# eCog118_Switches.net
KiCad netlist of a schematic drawn in EAGLE
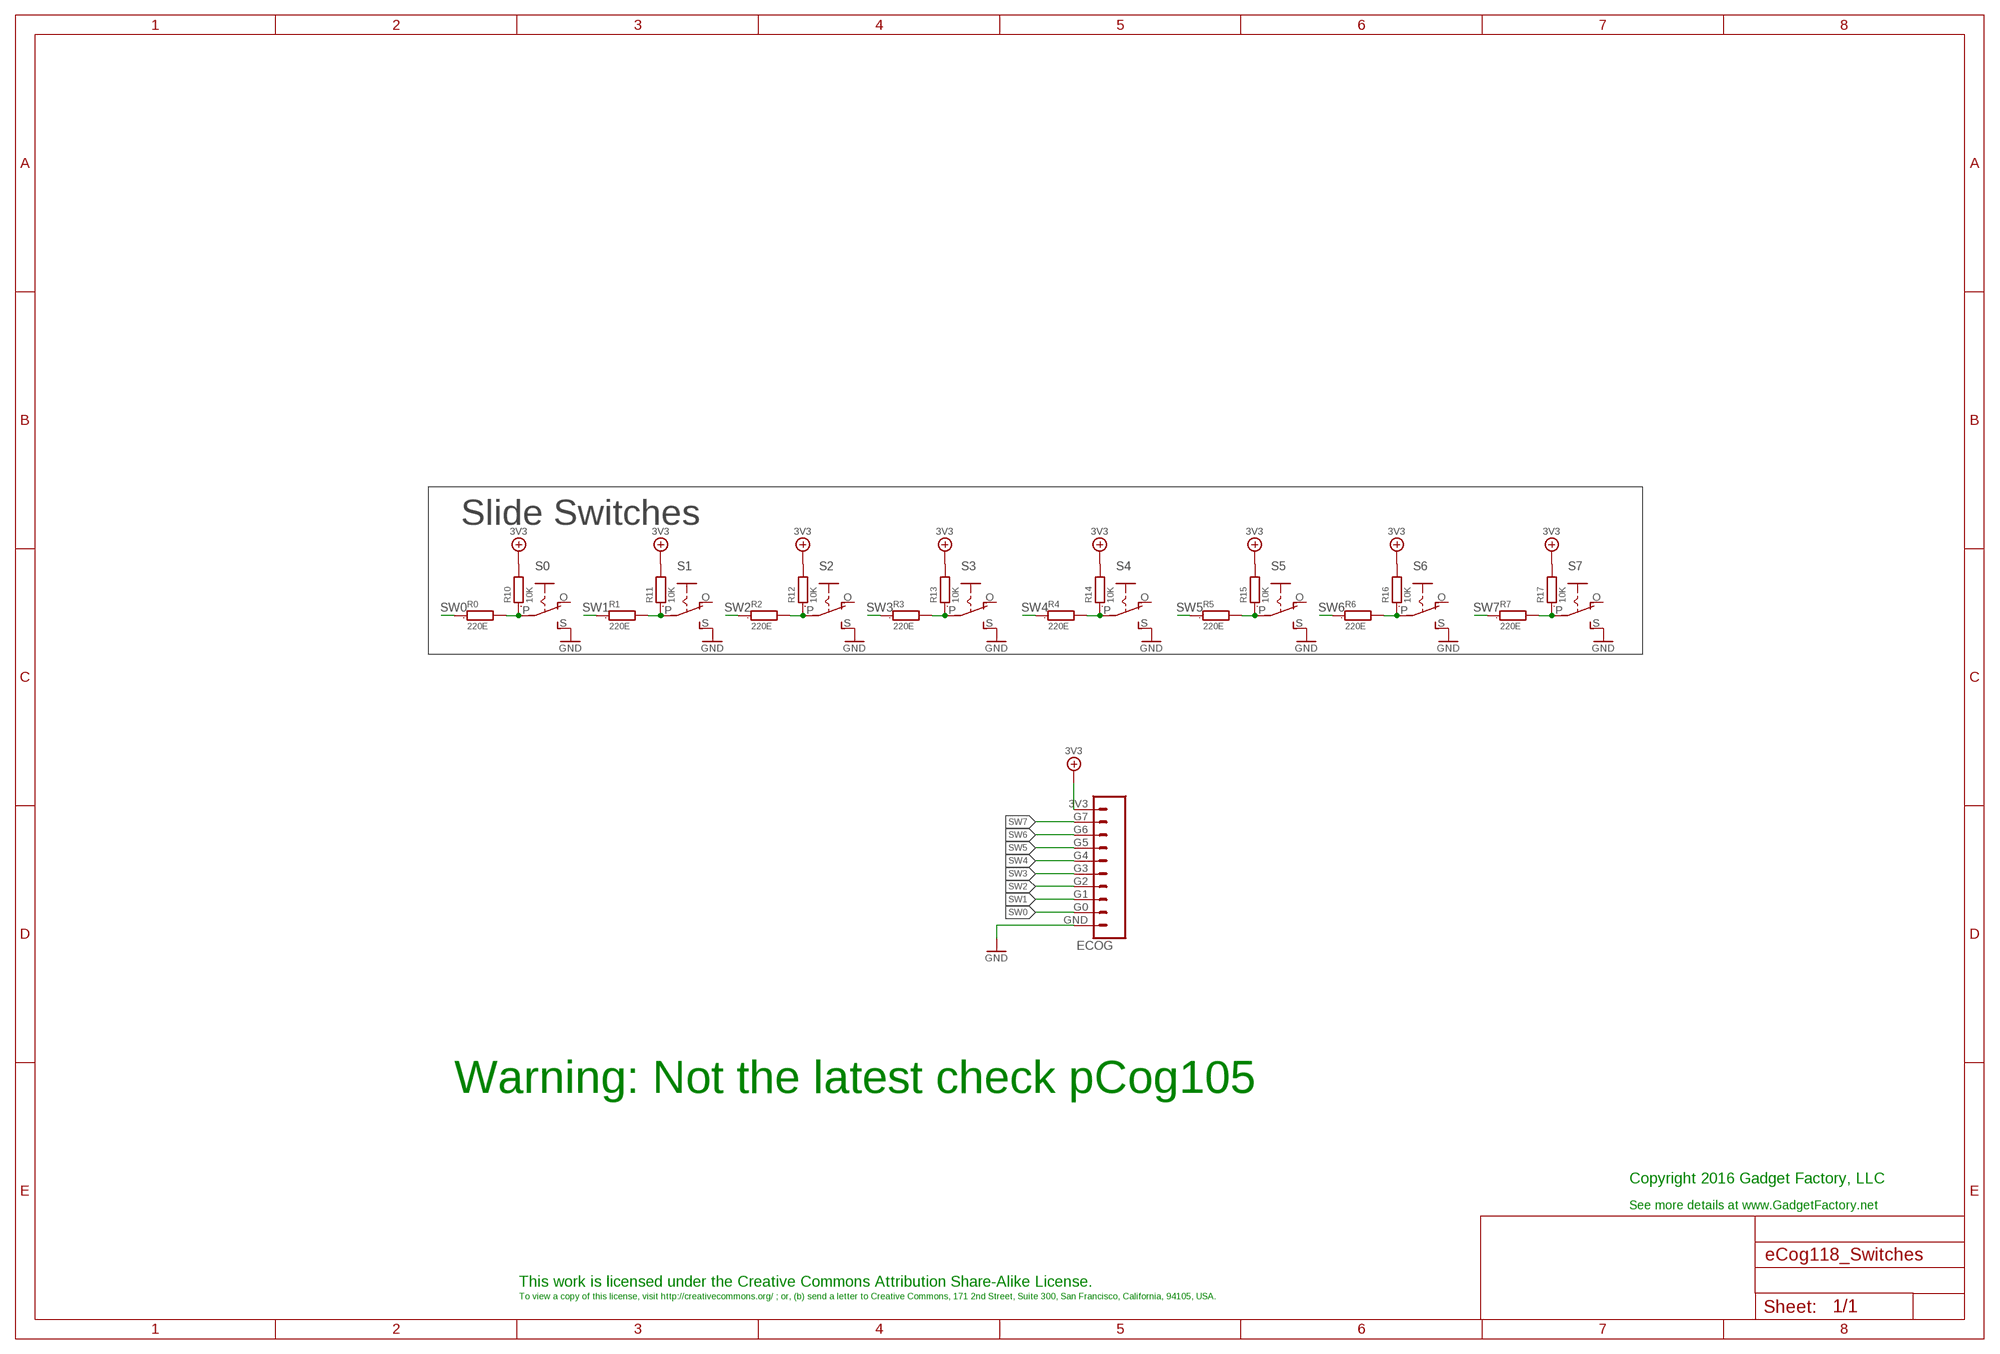
[diagram p0: schematic, sheet 1]

(export (version "E")
  (design (tool "Eeschema 10.0.6"))
  (components
    (comp (ref "ECOG")
      (value "ECOG_GENERAL_ROWTHROUGHOLE")
      (footprint "eagle-import:ECOG_GENERAL_TH")
      (libsource (lib "eagle-import") (part "ECOG_GENERAL_ROWTHROUGHOLE"))
    )
    (comp (ref "R0")
      (value "220E")
      (footprint "eagle-import:0603")
      (fields (field (name "PARTNO") "RMCF0603JT220R"))
      (libsource (lib "eagle-import") (part "R0603"))
    )
    (comp (ref "R1")
      (value "220E")
      (footprint "eagle-import:0603")
      (fields (field (name "PARTNO") "RMCF0603JT220R"))
      (libsource (lib "eagle-import") (part "R0603"))
    )
    (comp (ref "R2")
      (value "220E")
      (footprint "eagle-import:0603")
      (fields (field (name "PARTNO") "RMCF0603JT220R"))
      (libsource (lib "eagle-import") (part "R0603"))
    )
    (comp (ref "R3")
      (value "220E")
      (footprint "eagle-import:0603")
      (fields (field (name "PARTNO") "RMCF0603JT220R"))
      (libsource (lib "eagle-import") (part "R0603"))
    )
    (comp (ref "R4")
      (value "220E")
      (footprint "eagle-import:0603")
      (fields (field (name "PARTNO") "RMCF0603JT220R"))
      (libsource (lib "eagle-import") (part "R0603"))
    )
    (comp (ref "R5")
      (value "220E")
      (footprint "eagle-import:0603")
      (fields (field (name "PARTNO") "RMCF0603JT220R"))
      (libsource (lib "eagle-import") (part "R0603"))
    )
    (comp (ref "R6")
      (value "220E")
      (footprint "eagle-import:0603")
      (fields (field (name "PARTNO") "RMCF0603JT220R"))
      (libsource (lib "eagle-import") (part "R0603"))
    )
    (comp (ref "R7")
      (value "220E")
      (footprint "eagle-import:0603")
      (fields (field (name "PARTNO") "RMCF0603JT220R"))
      (libsource (lib "eagle-import") (part "R0603"))
    )
    (comp (ref "R10")
      (value "10K")
      (footprint "eagle-import:0603")
      (fields (field (name "PARTNO") "RMCF0603JT10K0"))
      (libsource (lib "eagle-import") (part "R0603"))
    )
    (comp (ref "R11")
      (value "10K")
      (footprint "eagle-import:0603")
      (fields (field (name "PARTNO") "RMCF0603JT10K0"))
      (libsource (lib "eagle-import") (part "R0603"))
    )
    (comp (ref "R12")
      (value "10K")
      (footprint "eagle-import:0603")
      (fields (field (name "PARTNO") "RMCF0603JT10K0"))
      (libsource (lib "eagle-import") (part "R0603"))
    )
    (comp (ref "R13")
      (value "10K")
      (footprint "eagle-import:0603")
      (fields (field (name "PARTNO") "RMCF0603JT10K0"))
      (libsource (lib "eagle-import") (part "R0603"))
    )
    (comp (ref "R14")
      (value "10K")
      (footprint "eagle-import:0603")
      (fields (field (name "PARTNO") "RMCF0603JT10K0"))
      (libsource (lib "eagle-import") (part "R0603"))
    )
    (comp (ref "R15")
      (value "10K")
      (footprint "eagle-import:0603")
      (fields (field (name "PARTNO") "RMCF0603JT10K0"))
      (libsource (lib "eagle-import") (part "R0603"))
    )
    (comp (ref "R16")
      (value "10K")
      (footprint "eagle-import:0603")
      (fields (field (name "PARTNO") "RMCF0603JT10K0"))
      (libsource (lib "eagle-import") (part "R0603"))
    )
    (comp (ref "R17")
      (value "10K")
      (footprint "eagle-import:0603")
      (fields (field (name "PARTNO") "RMCF0603JT10K0"))
      (libsource (lib "eagle-import") (part "R0603"))
    )
    (comp (ref "S0")
      (value "EG1218S")
      (footprint "eagle-import:EG1218")
      (fields (field (name "PARTNO") "EG1218"))
      (libsource (lib "eagle-import") (part "EG1218S"))
    )
    (comp (ref "S1")
      (value "EG1218S")
      (footprint "eagle-import:EG1218")
      (fields (field (name "PARTNO") "EG1218"))
      (libsource (lib "eagle-import") (part "EG1218S"))
    )
    (comp (ref "S2")
      (value "EG1218S")
      (footprint "eagle-import:EG1218")
      (fields (field (name "PARTNO") "EG1218"))
      (libsource (lib "eagle-import") (part "EG1218S"))
    )
    (comp (ref "S3")
      (value "EG1218S")
      (footprint "eagle-import:EG1218")
      (fields (field (name "PARTNO") "EG1218"))
      (libsource (lib "eagle-import") (part "EG1218S"))
    )
    (comp (ref "S4")
      (value "EG1218S")
      (footprint "eagle-import:EG1218")
      (fields (field (name "PARTNO") "EG1218"))
      (libsource (lib "eagle-import") (part "EG1218S"))
    )
    (comp (ref "S5")
      (value "EG1218S")
      (footprint "eagle-import:EG1218")
      (fields (field (name "PARTNO") "EG1218"))
      (libsource (lib "eagle-import") (part "EG1218S"))
    )
    (comp (ref "S6")
      (value "EG1218S")
      (footprint "eagle-import:EG1218")
      (fields (field (name "PARTNO") "EG1218"))
      (libsource (lib "eagle-import") (part "EG1218S"))
    )
    (comp (ref "S7")
      (value "EG1218S")
      (footprint "eagle-import:EG1218")
      (fields (field (name "PARTNO") "EG1218"))
      (libsource (lib "eagle-import") (part "EG1218S"))
    )
  )
  (nets
    (net (code "1") (name "3V3") (class "Default")
      (node (ref "ECOG") (pin "3V3") (pinfunction "3V3_3V3") (pintype "power_in"))
      (node (ref "R10") (pin "2") (pinfunction "2_2") (pintype "passive"))
      (node (ref "R11") (pin "2") (pinfunction "2_2") (pintype "passive"))
      (node (ref "R12") (pin "2") (pinfunction "2_2") (pintype "passive"))
      (node (ref "R13") (pin "2") (pinfunction "2_2") (pintype "passive"))
      (node (ref "R14") (pin "2") (pinfunction "2_2") (pintype "passive"))
      (node (ref "R15") (pin "2") (pinfunction "2_2") (pintype "passive"))
      (node (ref "R16") (pin "2") (pinfunction "2_2") (pintype "passive"))
      (node (ref "R17") (pin "2") (pinfunction "2_2") (pintype "passive"))
    )
    (net (code "2") (name "GND") (class "Default")
      (node (ref "ECOG") (pin "GND") (pinfunction "GND_GND") (pintype "power_in"))
      (node (ref "S0") (pin "S") (pinfunction "S_S") (pintype "passive"))
      (node (ref "S1") (pin "S") (pinfunction "S_S") (pintype "passive"))
      (node (ref "S2") (pin "S") (pinfunction "S_S") (pintype "passive"))
      (node (ref "S3") (pin "S") (pinfunction "S_S") (pintype "passive"))
      (node (ref "S4") (pin "S") (pinfunction "S_S") (pintype "passive"))
      (node (ref "S5") (pin "S") (pinfunction "S_S") (pintype "passive"))
      (node (ref "S6") (pin "S") (pinfunction "S_S") (pintype "passive"))
      (node (ref "S7") (pin "S") (pinfunction "S_S") (pintype "passive"))
    )
    (net (code "3") (name "Net-(R0-Pad2)") (class "Default")
      (node (ref "R0") (pin "2") (pinfunction "2_2") (pintype "passive"))
      (node (ref "R10") (pin "1") (pinfunction "1_1") (pintype "passive"))
      (node (ref "S0") (pin "P") (pinfunction "P_P") (pintype "passive"))
    )
    (net (code "4") (name "Net-(R1-Pad2)") (class "Default")
      (node (ref "R1") (pin "2") (pinfunction "2_2") (pintype "passive"))
      (node (ref "R11") (pin "1") (pinfunction "1_1") (pintype "passive"))
      (node (ref "S1") (pin "P") (pinfunction "P_P") (pintype "passive"))
    )
    (net (code "5") (name "Net-(R12-Pad1)") (class "Default")
      (node (ref "R12") (pin "1") (pinfunction "1_1") (pintype "passive"))
      (node (ref "R2") (pin "2") (pinfunction "2_2") (pintype "passive"))
      (node (ref "S2") (pin "P") (pinfunction "P_P") (pintype "passive"))
    )
    (net (code "6") (name "Net-(R13-Pad1)") (class "Default")
      (node (ref "R13") (pin "1") (pinfunction "1_1") (pintype "passive"))
      (node (ref "R3") (pin "2") (pinfunction "2_2") (pintype "passive"))
      (node (ref "S3") (pin "P") (pinfunction "P_P") (pintype "passive"))
    )
    (net (code "7") (name "Net-(R14-Pad1)") (class "Default")
      (node (ref "R14") (pin "1") (pinfunction "1_1") (pintype "passive"))
      (node (ref "R4") (pin "2") (pinfunction "2_2") (pintype "passive"))
      (node (ref "S4") (pin "P") (pinfunction "P_P") (pintype "passive"))
    )
    (net (code "8") (name "Net-(R15-Pad1)") (class "Default")
      (node (ref "R15") (pin "1") (pinfunction "1_1") (pintype "passive"))
      (node (ref "R5") (pin "2") (pinfunction "2_2") (pintype "passive"))
      (node (ref "S5") (pin "P") (pinfunction "P_P") (pintype "passive"))
    )
    (net (code "9") (name "Net-(R16-Pad1)") (class "Default")
      (node (ref "R16") (pin "1") (pinfunction "1_1") (pintype "passive"))
      (node (ref "R6") (pin "2") (pinfunction "2_2") (pintype "passive"))
      (node (ref "S6") (pin "P") (pinfunction "P_P") (pintype "passive"))
    )
    (net (code "10") (name "Net-(R17-Pad1)") (class "Default")
      (node (ref "R17") (pin "1") (pinfunction "1_1") (pintype "passive"))
      (node (ref "R7") (pin "2") (pinfunction "2_2") (pintype "passive"))
      (node (ref "S7") (pin "P") (pinfunction "P_P") (pintype "passive"))
    )
    (net (code "11") (name "SW0") (class "Default")
      (node (ref "ECOG") (pin "G0") (pinfunction "G0_G0") (pintype "passive"))
      (node (ref "R0") (pin "1") (pinfunction "1_1") (pintype "passive"))
    )
    (net (code "12") (name "SW1") (class "Default")
      (node (ref "ECOG") (pin "G1") (pinfunction "G1_G1") (pintype "passive"))
      (node (ref "R1") (pin "1") (pinfunction "1_1") (pintype "passive"))
    )
    (net (code "13") (name "SW2") (class "Default")
      (node (ref "ECOG") (pin "G2") (pinfunction "G2_G2") (pintype "passive"))
      (node (ref "R2") (pin "1") (pinfunction "1_1") (pintype "passive"))
    )
    (net (code "14") (name "SW3") (class "Default")
      (node (ref "ECOG") (pin "G3") (pinfunction "G3_G3") (pintype "passive"))
      (node (ref "R3") (pin "1") (pinfunction "1_1") (pintype "passive"))
    )
    (net (code "15") (name "SW4") (class "Default")
      (node (ref "ECOG") (pin "G4") (pinfunction "G4_G4") (pintype "passive"))
      (node (ref "R4") (pin "1") (pinfunction "1_1") (pintype "passive"))
    )
    (net (code "16") (name "SW5") (class "Default")
      (node (ref "ECOG") (pin "G5") (pinfunction "G5_G5") (pintype "passive"))
      (node (ref "R5") (pin "1") (pinfunction "1_1") (pintype "passive"))
    )
    (net (code "17") (name "SW6") (class "Default")
      (node (ref "ECOG") (pin "G6") (pinfunction "G6_G6") (pintype "passive"))
      (node (ref "R6") (pin "1") (pinfunction "1_1") (pintype "passive"))
    )
    (net (code "18") (name "SW7") (class "Default")
      (node (ref "ECOG") (pin "G7") (pinfunction "G7_G7") (pintype "passive"))
      (node (ref "R7") (pin "1") (pinfunction "1_1") (pintype "passive"))
    )
    (net (code "19") (name "unconnected-(S0-PadO)") (class "Default")
      (node (ref "S0") (pin "O") (pinfunction "O_O") (pintype "passive"))
    )
    (net (code "20") (name "unconnected-(S1-PadO)") (class "Default")
      (node (ref "S1") (pin "O") (pinfunction "O_O") (pintype "passive"))
    )
    (net (code "21") (name "unconnected-(S2-PadO)") (class "Default")
      (node (ref "S2") (pin "O") (pinfunction "O_O") (pintype "passive"))
    )
    (net (code "22") (name "unconnected-(S3-PadO)") (class "Default")
      (node (ref "S3") (pin "O") (pinfunction "O_O") (pintype "passive"))
    )
    (net (code "23") (name "unconnected-(S4-PadO)") (class "Default")
      (node (ref "S4") (pin "O") (pinfunction "O_O") (pintype "passive"))
    )
    (net (code "24") (name "unconnected-(S5-PadO)") (class "Default")
      (node (ref "S5") (pin "O") (pinfunction "O_O") (pintype "passive"))
    )
    (net (code "25") (name "unconnected-(S6-PadO)") (class "Default")
      (node (ref "S6") (pin "O") (pinfunction "O_O") (pintype "passive"))
    )
    (net (code "26") (name "unconnected-(S7-PadO)") (class "Default")
      (node (ref "S7") (pin "O") (pinfunction "O_O") (pintype "passive"))
    )
  )
)
